# CON_RS232DCE_DB9_TH.net
KiCad netlist of a schematic drawn in Altium Designer
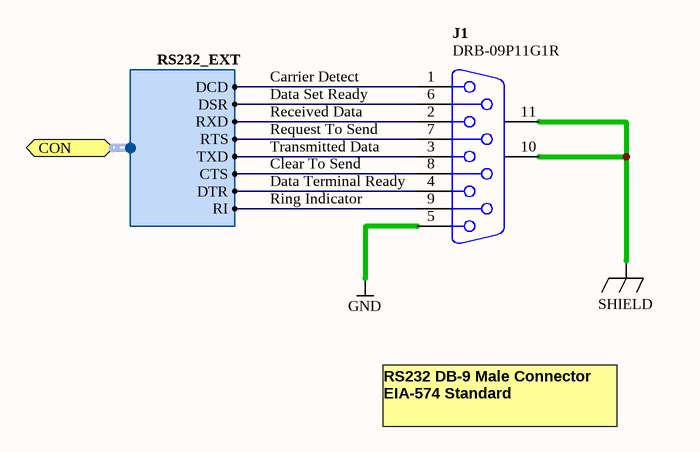
[diagram p0: CON_RS232DCE_DB9_TH.SchDoc]

(export (version "E")
  (design (tool "Eeschema 10.0.6"))
  (components
    (comp (ref "J1")
      (value "DRB-09P11G1R")
      (footprint "DB9_MALE")
      (description "Connector, DB9 R/A Through-hole Male")
      (libsource (lib "AltiumDesignLibrary") (part "CON-DB-9-M-RA"))
    )
  )
  (nets
    (net (code "2") (name "/CTS") (class "Default")
      (node (ref "J1") (pin "8") (pinfunction "8_8") (pintype "passive"))
    )
    (net (code "3") (name "/DCD") (class "Default")
      (node (ref "J1") (pin "1") (pinfunction "1_1") (pintype "passive"))
    )
    (net (code "4") (name "/DSR") (class "Default")
      (node (ref "J1") (pin "6") (pinfunction "6_6") (pintype "passive"))
    )
    (net (code "5") (name "/DTR") (class "Default")
      (node (ref "J1") (pin "4") (pinfunction "4_4") (pintype "passive"))
    )
    (net (code "6") (name "/RI") (class "Default")
      (node (ref "J1") (pin "9") (pinfunction "9_9") (pintype "passive"))
    )
    (net (code "7") (name "/RTS") (class "Default")
      (node (ref "J1") (pin "7") (pinfunction "7_7") (pintype "passive"))
    )
    (net (code "8") (name "/RXD") (class "Default")
      (node (ref "J1") (pin "2") (pinfunction "2_2") (pintype "passive"))
    )
    (net (code "9") (name "/TXD") (class "Default")
      (node (ref "J1") (pin "3") (pinfunction "3_3") (pintype "passive"))
    )
    (net (code "11") (name "GND") (class "Default")
      (node (ref "J1") (pin "5") (pinfunction "5_5") (pintype "passive"))
    )
    (net (code "12") (name "SHIELD") (class "Default")
      (node (ref "J1") (pin "10") (pinfunction "MH1_10") (pintype "passive"))
      (node (ref "J1") (pin "11") (pinfunction "MH2_11") (pintype "passive"))
    )
  )
)
